# Input_output_Connectors.net
KiCad netlist of a schematic drawn in Altium Designer
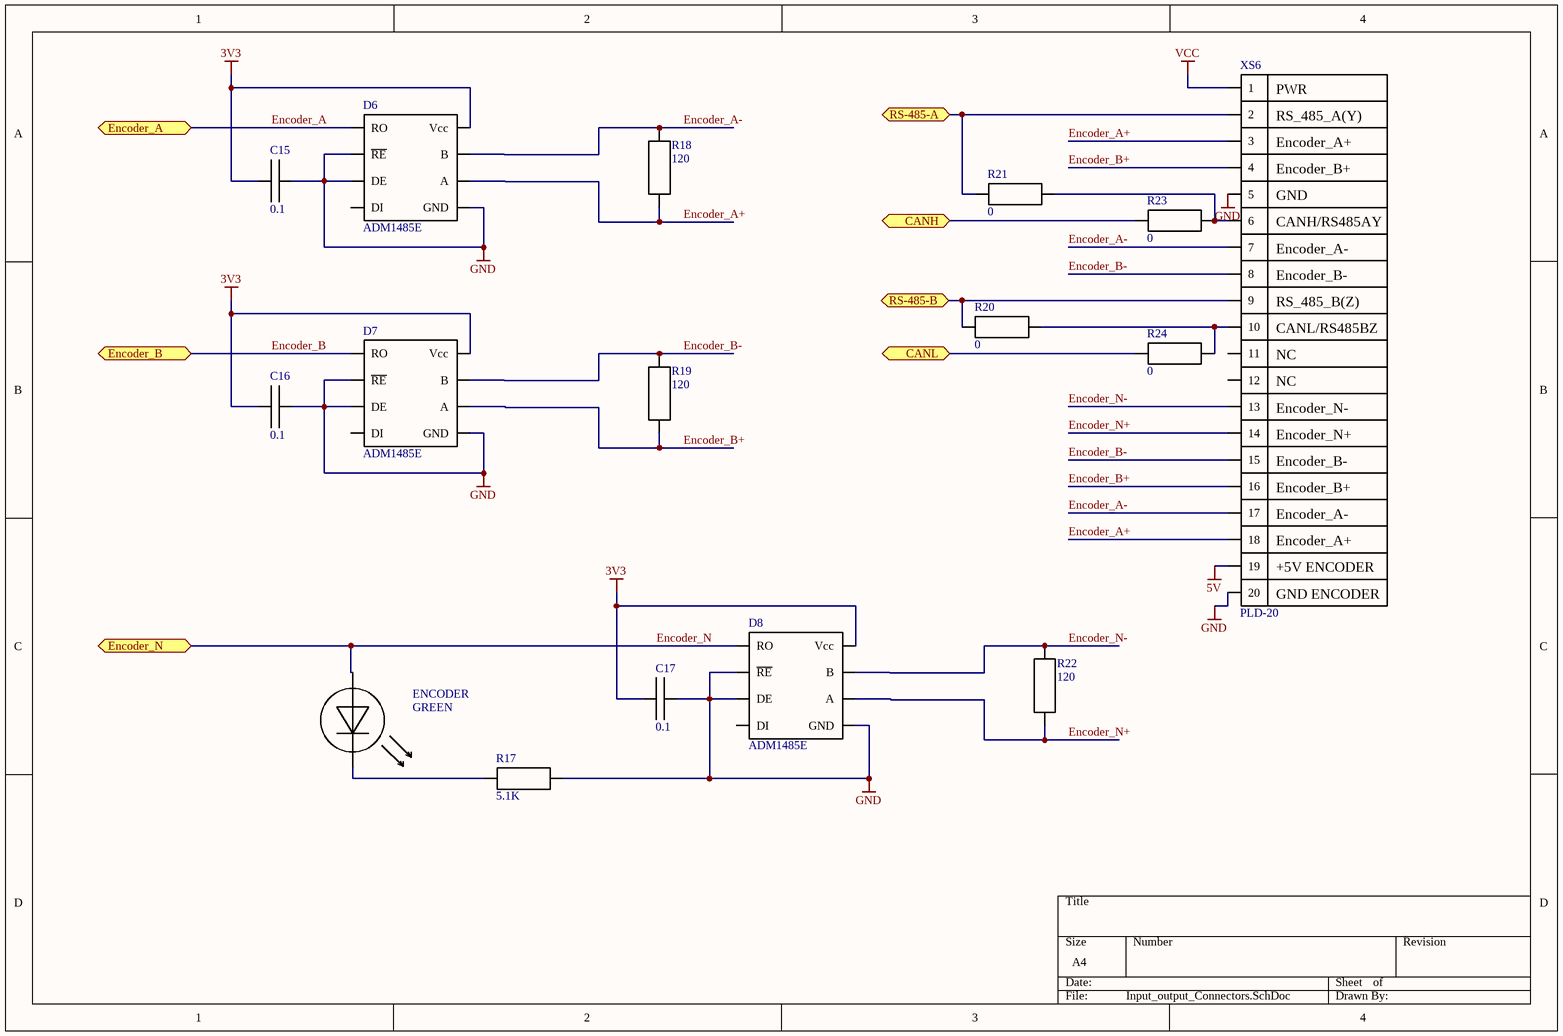
[diagram p0: Input_output_Connectors.SchDoc]

(export (version "E")
  (design (tool "Eeschema 10.0.6"))
  (components
    (comp (ref "C15")
      (value "0.1")
      (footprint "Mylibrary:SMD_0402_C")
      (libsource (lib "Mylibrary") (part "Capacitor"))
    )
    (comp (ref "C16")
      (value "0.1")
      (footprint "Mylibrary:SMD_0402_C")
      (libsource (lib "Mylibrary") (part "Capacitor"))
    )
    (comp (ref "C17")
      (value "0.1")
      (footprint "Mylibrary:SMD_0402_C")
      (libsource (lib "Mylibrary") (part "Capacitor"))
    )
    (comp (ref "D6")
      (value "ADM1485E")
      (footprint "Mylibrary:SOIC_N 8-Lead")
      (libsource (lib "Mylibrary") (part "ADM1485"))
    )
    (comp (ref "D7")
      (value "ADM1485E")
      (footprint "Mylibrary:SOIC_N 8-Lead")
      (libsource (lib "Mylibrary") (part "ADM1485"))
    )
    (comp (ref "D8")
      (value "ADM1485E")
      (footprint "Mylibrary:SOIC_N 8-Lead")
      (libsource (lib "Mylibrary") (part "ADM1485"))
    )
    (comp (ref "ENCODER")
      (value "GREEN")
      (footprint "Mylibrary:SMD_LED")
      (libsource (lib "Mylibrary") (part "LED_Diode"))
    )
    (comp (ref "R17")
      (value "5.1K")
      (footprint "SMD_0603")
      (description "0603 resistor")
      (libsource (lib "Mylibrary") (part "Resistor"))
    )
    (comp (ref "R18")
      (value "120")
      (footprint "SMD_0603")
      (description "0603 resistor")
      (libsource (lib "Mylibrary") (part "Resistor"))
    )
    (comp (ref "R19")
      (value "120")
      (footprint "SMD_0603")
      (description "0603 resistor")
      (libsource (lib "Mylibrary") (part "Resistor"))
    )
    (comp (ref "R20")
      (value "0")
      (footprint "SMD_0603")
      (description "dont fitting")
      (libsource (lib "Mylibrary") (part "Resistor"))
    )
    (comp (ref "R21")
      (value "0")
      (footprint "SMD_0603")
      (description "dont fitting")
      (libsource (lib "Mylibrary") (part "Resistor"))
    )
    (comp (ref "R22")
      (value "120")
      (footprint "SMD_0603")
      (description "0603 resistor")
      (libsource (lib "Mylibrary") (part "Resistor"))
    )
    (comp (ref "R23") (value "0") (footprint "SMD_0603") (libsource (lib "Mylibrary") (part "Resistor")))
    (comp (ref "R24") (value "0") (footprint "SMD_0603") (libsource (lib "Mylibrary") (part "Resistor")))
    (comp (ref "XS6")
      (value "PLD-20")
      (footprint "Mylibrary:IDC2.54-20")
      (description "HSOW2 encoder and external connector")
      (libsource (lib "Mylibrary") (part "PLD-20"))
    )
  )
  (nets
    (net (code "1") (name "/CANH") (class "Default")
      (node (ref "R23") (pin "1") (pinfunction "1_1") (pintype "passive"))
    )
    (net (code "2") (name "/CANL") (class "Default")
      (node (ref "R24") (pin "1") (pinfunction "1_1") (pintype "passive"))
    )
    (net (code "3") (name "/Encoder_A") (class "Default")
      (node (ref "D6") (pin "1") (pinfunction "RO_1") (pintype "passive"))
    )
    (net (code "4") (name "/Encoder_A+") (class "Default")
      (node (ref "D6") (pin "6") (pinfunction "A_6") (pintype "passive"))
      (node (ref "R18") (pin "1") (pinfunction "1_1") (pintype "passive"))
      (node (ref "XS6") (pin "18") (pinfunction "18_18") (pintype "passive"))
      (node (ref "XS6") (pin "3") (pinfunction "3_3") (pintype "passive"))
    )
    (net (code "5") (name "/Encoder_A-") (class "Default")
      (node (ref "D6") (pin "7") (pinfunction "B_7") (pintype "passive"))
      (node (ref "R18") (pin "2") (pinfunction "2_2") (pintype "passive"))
      (node (ref "XS6") (pin "17") (pinfunction "17_17") (pintype "passive"))
      (node (ref "XS6") (pin "7") (pinfunction "7_7") (pintype "passive"))
    )
    (net (code "6") (name "/Encoder_B") (class "Default")
      (node (ref "D7") (pin "1") (pinfunction "RO_1") (pintype "passive"))
    )
    (net (code "7") (name "/Encoder_B+") (class "Default")
      (node (ref "D7") (pin "6") (pinfunction "A_6") (pintype "passive"))
      (node (ref "R19") (pin "1") (pinfunction "1_1") (pintype "passive"))
      (node (ref "XS6") (pin "16") (pinfunction "16_16") (pintype "passive"))
      (node (ref "XS6") (pin "4") (pinfunction "4_4") (pintype "passive"))
    )
    (net (code "8") (name "/Encoder_B-") (class "Default")
      (node (ref "D7") (pin "7") (pinfunction "B_7") (pintype "passive"))
      (node (ref "R19") (pin "2") (pinfunction "2_2") (pintype "passive"))
      (node (ref "XS6") (pin "15") (pinfunction "15_15") (pintype "passive"))
      (node (ref "XS6") (pin "8") (pinfunction "8_8") (pintype "passive"))
    )
    (net (code "9") (name "/Encoder_N") (class "Default")
      (node (ref "D8") (pin "1") (pinfunction "RO_1") (pintype "passive"))
      (node (ref "ENCODER") (pin "2") (pintype "passive"))
    )
    (net (code "10") (name "/Encoder_N+") (class "Default")
      (node (ref "D8") (pin "6") (pinfunction "A_6") (pintype "passive"))
      (node (ref "R22") (pin "1") (pinfunction "1_1") (pintype "passive"))
      (node (ref "XS6") (pin "14") (pinfunction "14_14") (pintype "passive"))
    )
    (net (code "11") (name "/Encoder_N-") (class "Default")
      (node (ref "D8") (pin "7") (pinfunction "B_7") (pintype "passive"))
      (node (ref "R22") (pin "2") (pinfunction "2_2") (pintype "passive"))
      (node (ref "XS6") (pin "13") (pinfunction "13_13") (pintype "passive"))
    )
    (net (code "12") (name "/RS-485-A") (class "Default")
      (node (ref "R21") (pin "1") (pinfunction "1_1") (pintype "passive"))
      (node (ref "XS6") (pin "2") (pinfunction "2_2") (pintype "passive"))
    )
    (net (code "13") (name "/RS-485-B") (class "Default")
      (node (ref "R20") (pin "1") (pinfunction "1_1") (pintype "passive"))
      (node (ref "XS6") (pin "9") (pinfunction "9_9") (pintype "passive"))
    )
    (net (code "14") (name "3V3") (class "Default")
      (node (ref "C15") (pin "1") (pinfunction "1_1") (pintype "passive"))
      (node (ref "C16") (pin "1") (pinfunction "1_1") (pintype "passive"))
      (node (ref "C17") (pin "1") (pinfunction "1_1") (pintype "passive"))
      (node (ref "D6") (pin "8") (pinfunction "Vcc_8") (pintype "passive"))
      (node (ref "D7") (pin "8") (pinfunction "Vcc_8") (pintype "passive"))
      (node (ref "D8") (pin "8") (pinfunction "Vcc_8") (pintype "passive"))
    )
    (net (code "15") (name "5V") (class "Default")
      (node (ref "XS6") (pin "19") (pinfunction "19_19") (pintype "passive"))
    )
    (net (code "16") (name "GND") (class "Default")
      (node (ref "C15") (pin "2") (pinfunction "2_2") (pintype "passive"))
      (node (ref "C16") (pin "2") (pinfunction "2_2") (pintype "passive"))
      (node (ref "C17") (pin "2") (pinfunction "2_2") (pintype "passive"))
      (node (ref "D6") (pin "2") (pinfunction "~{RE}_2") (pintype "passive"))
      (node (ref "D6") (pin "3") (pinfunction "DE_3") (pintype "passive"))
      (node (ref "D6") (pin "5") (pinfunction "GND_5") (pintype "passive"))
      (node (ref "D7") (pin "2") (pinfunction "~{RE}_2") (pintype "passive"))
      (node (ref "D7") (pin "3") (pinfunction "DE_3") (pintype "passive"))
      (node (ref "D7") (pin "5") (pinfunction "GND_5") (pintype "passive"))
      (node (ref "D8") (pin "2") (pinfunction "~{RE}_2") (pintype "passive"))
      (node (ref "D8") (pin "3") (pinfunction "DE_3") (pintype "passive"))
      (node (ref "D8") (pin "5") (pinfunction "GND_5") (pintype "passive"))
      (node (ref "R17") (pin "2") (pinfunction "2_2") (pintype "passive"))
      (node (ref "XS6") (pin "20") (pinfunction "20_20") (pintype "passive"))
      (node (ref "XS6") (pin "5") (pinfunction "5_5") (pintype "passive"))
    )
    (net (code "17") (name "Net-(ENCODER-Pad1)") (class "Default")
      (node (ref "ENCODER") (pin "1") (pintype "passive"))
      (node (ref "R17") (pin "1") (pinfunction "1_1") (pintype "passive"))
    )
    (net (code "18") (name "Net-(R20-Pad2)") (class "Default")
      (node (ref "R20") (pin "2") (pinfunction "2_2") (pintype "passive"))
      (node (ref "R24") (pin "2") (pinfunction "2_2") (pintype "passive"))
      (node (ref "XS6") (pin "10") (pinfunction "10_10") (pintype "passive"))
    )
    (net (code "19") (name "Net-(R21-Pad2)") (class "Default")
      (node (ref "R21") (pin "2") (pinfunction "2_2") (pintype "passive"))
      (node (ref "R23") (pin "2") (pinfunction "2_2") (pintype "passive"))
      (node (ref "XS6") (pin "6") (pinfunction "6_6") (pintype "passive"))
    )
    (net (code "20") (name "VCC") (class "Default")
      (node (ref "XS6") (pin "1") (pinfunction "1_1") (pintype "passive"))
    )
    (net (code "21") (name "unconnected-(D6-DI-Pad4)") (class "Default")
      (node (ref "D6") (pin "4") (pinfunction "DI_4") (pintype "passive"))
    )
    (net (code "22") (name "unconnected-(D7-DI-Pad4)") (class "Default")
      (node (ref "D7") (pin "4") (pinfunction "DI_4") (pintype "passive"))
    )
    (net (code "23") (name "unconnected-(D8-DI-Pad4)") (class "Default")
      (node (ref "D8") (pin "4") (pinfunction "DI_4") (pintype "passive"))
    )
    (net (code "24") (name "unconnected-(XS6-Pad11)") (class "Default")
      (node (ref "XS6") (pin "11") (pinfunction "11_11") (pintype "passive"))
    )
    (net (code "25") (name "unconnected-(XS6-Pad12)") (class "Default")
      (node (ref "XS6") (pin "12") (pinfunction "12_12") (pintype "passive"))
    )
  )
)
